# SCH_12V-DC-Distribute_2025-02-16_1.net
KiCad netlist of a schematic drawn in EasyEDA
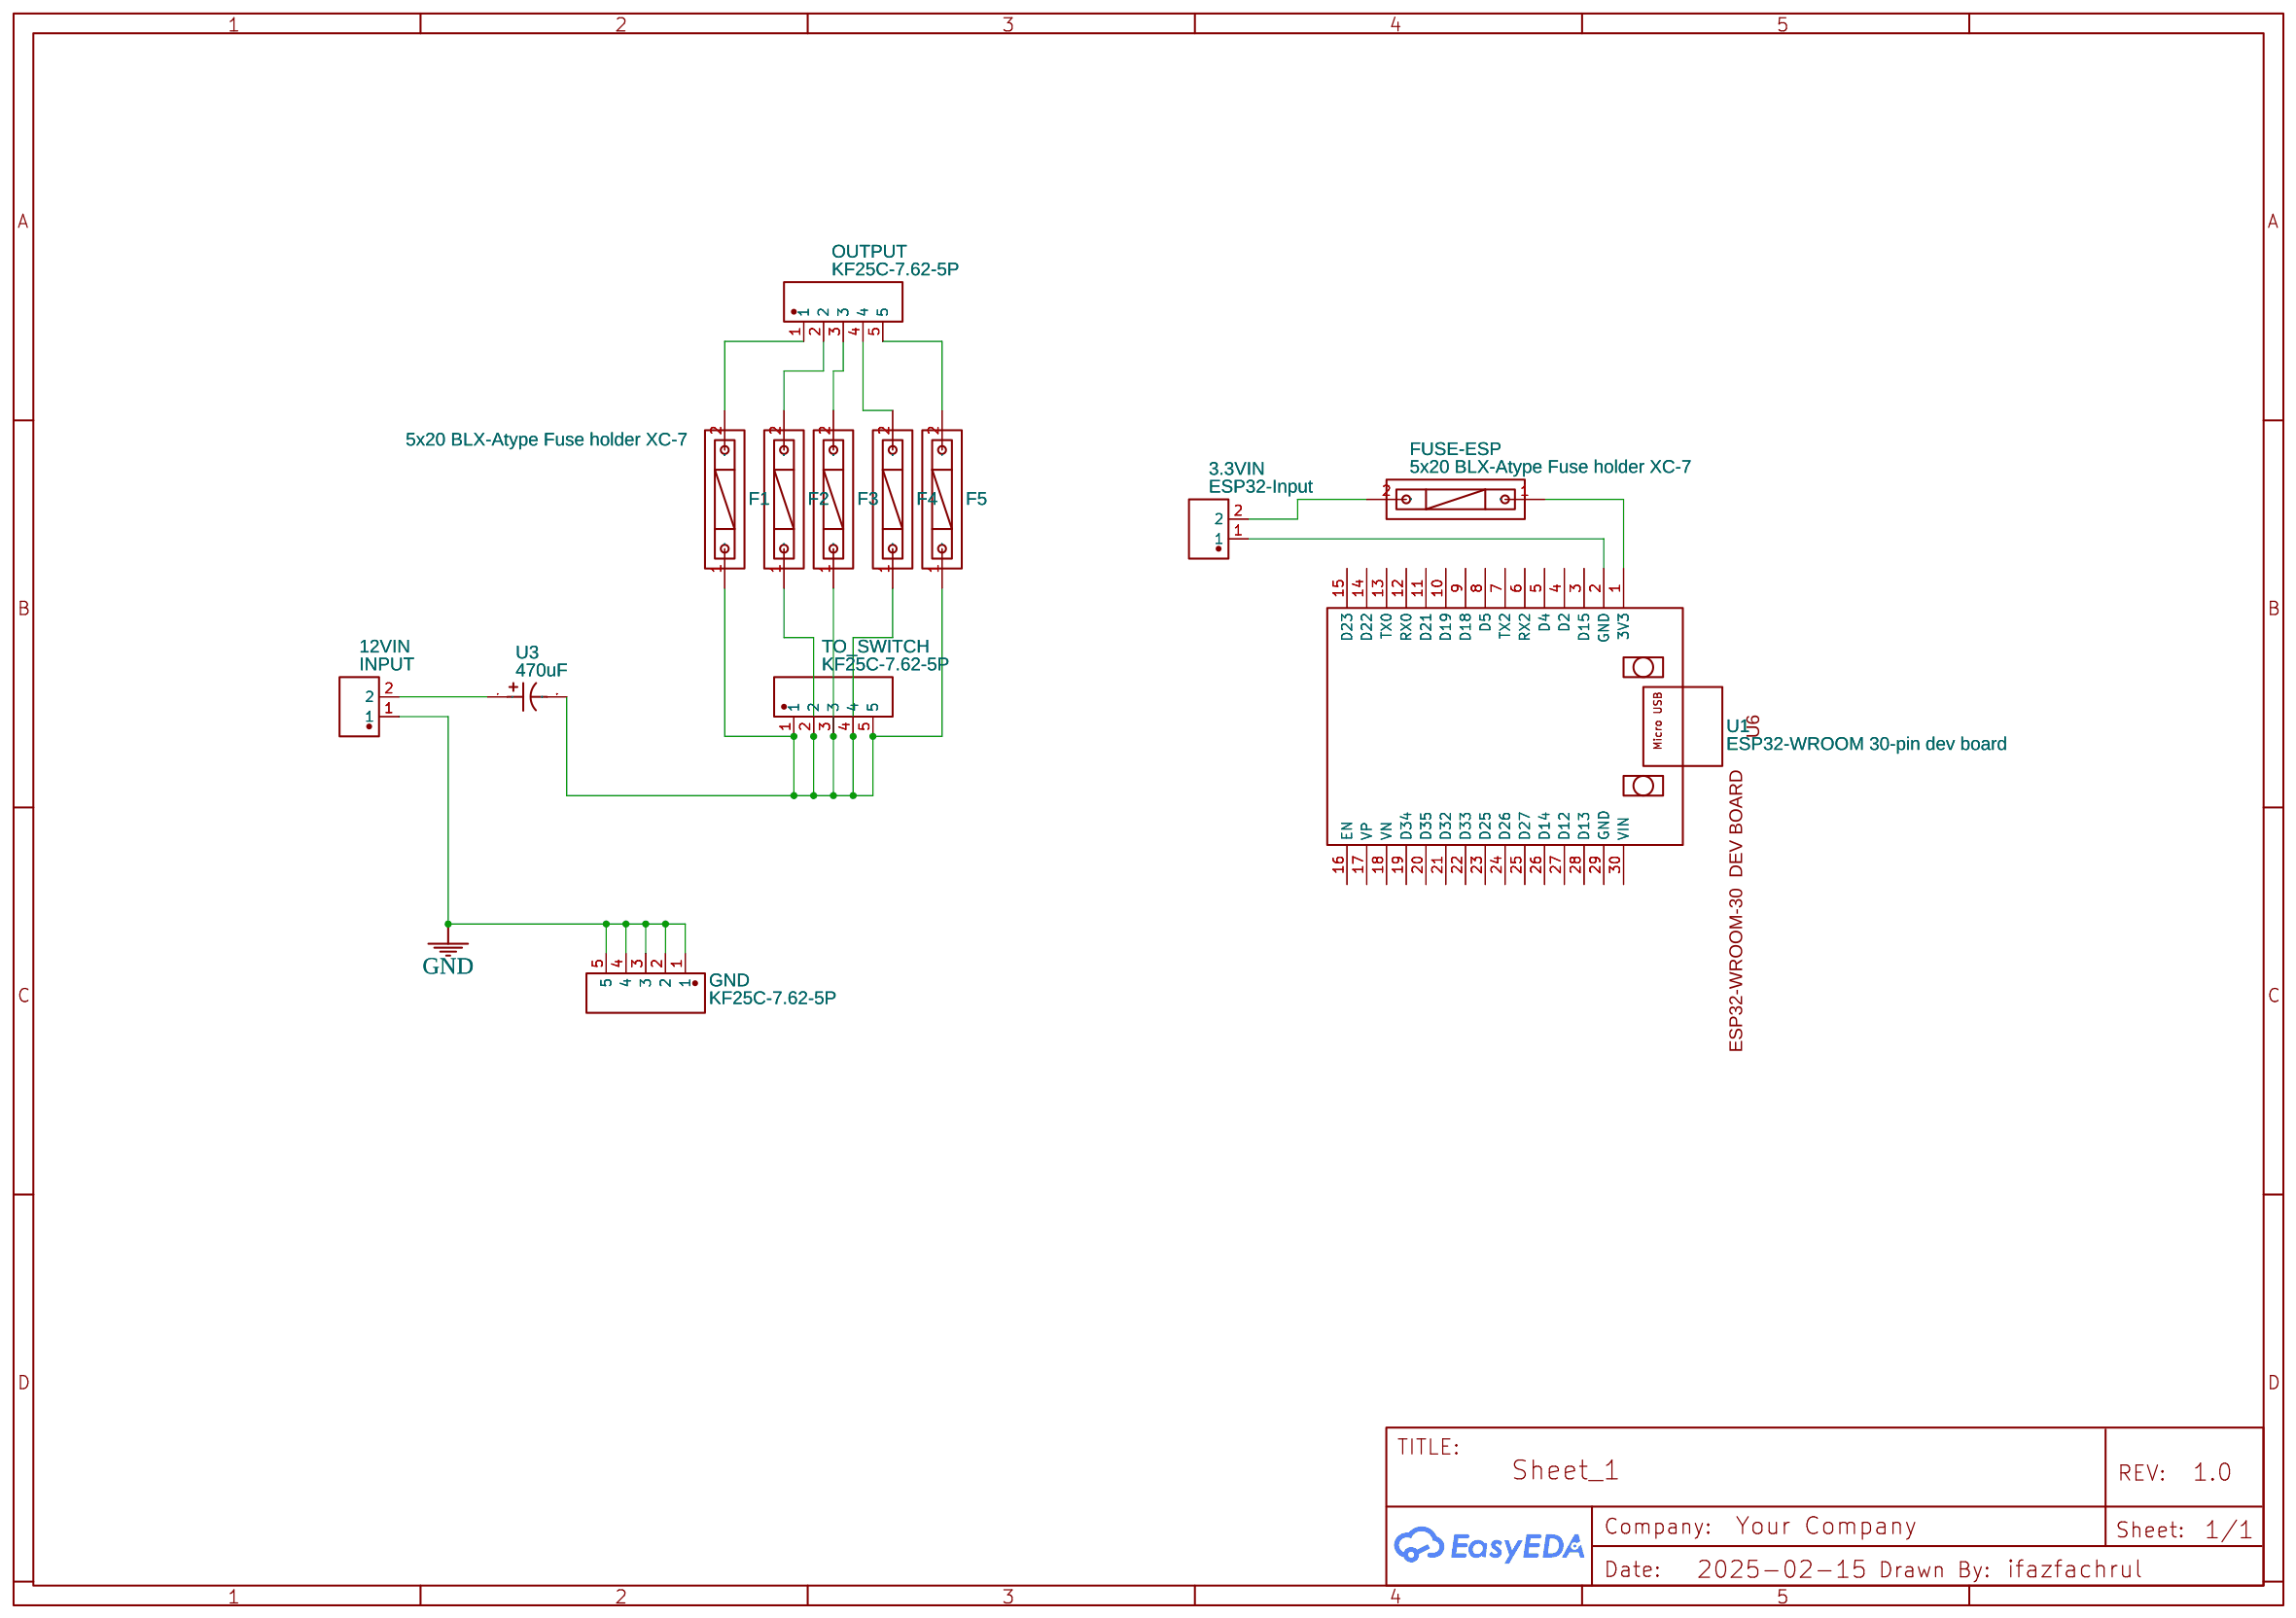
[diagram p0: schematic sheet]

(export (version "E")
  (design (tool "Eeschema 10.0.6"))
  (components
    (comp (ref "3.3VIN")
      (value "ESP32-Input")
      (fields (field (name "Manufacturer Part") "KF25H-7.62-2P") (field (name "Manufacturer") "KEFA(科发)"))
      (libsource (lib "") (part "KF25H-7.62-2P"))
    )
    (comp (ref "12VIN")
      (value "INPUT")
      (fields (field (name "Manufacturer Part") "KF25H-7.62-2P") (field (name "Manufacturer") "KEFA(科发)"))
      (libsource (lib "") (part "KF25H-7.62-2P_1"))
    )
    (comp (ref "F1")
      (value "5x20 BLX-Atype Fuse holder XC-7")
      (fields
        (field (name "Manufacturer Part") "5x20 BLX-A型 保险丝支架 XC-7")
        (field (name "Manufacturer") "xcfuse(旭程)")
      )
      (libsource (lib "") (part "5x20 BLX-Atype Fuse holder XC-7"))
    )
    (comp (ref "F2")
      (value "5x20 BLX-Atype Fuse holder XC-7")
      (fields
        (field (name "Manufacturer Part") "5x20 BLX-A型 保险丝支架 XC-7")
        (field (name "Manufacturer") "xcfuse(旭程)")
      )
      (libsource (lib "") (part "5x20 BLX-Atype Fuse holder XC-7"))
    )
    (comp (ref "F3")
      (value "5x20 BLX-Atype Fuse holder XC-7")
      (fields
        (field (name "Manufacturer Part") "5x20 BLX-A型 保险丝支架 XC-7")
        (field (name "Manufacturer") "xcfuse(旭程)")
      )
      (libsource (lib "") (part "5x20 BLX-Atype Fuse holder XC-7"))
    )
    (comp (ref "F4")
      (value "5x20 BLX-Atype Fuse holder XC-7")
      (fields
        (field (name "Manufacturer Part") "5x20 BLX-A型 保险丝支架 XC-7")
        (field (name "Manufacturer") "xcfuse(旭程)")
      )
      (libsource (lib "") (part "5x20 BLX-Atype Fuse holder XC-7"))
    )
    (comp (ref "F5")
      (value "5x20 BLX-Atype Fuse holder XC-7")
      (fields
        (field (name "Manufacturer Part") "5x20 BLX-A型 保险丝支架 XC-7")
        (field (name "Manufacturer") "xcfuse(旭程)")
      )
      (libsource (lib "") (part "5x20 BLX-Atype Fuse holder XC-7"))
    )
    (comp (ref "FUSE-ESP")
      (value "5x20 BLX-Atype Fuse holder XC-7")
      (fields
        (field (name "Manufacturer Part") "5x20 BLX-A型 保险丝支架 XC-7")
        (field (name "Manufacturer") "xcfuse(旭程)")
      )
      (libsource (lib "") (part "5x20 BLX-Atype Fuse holder XC-7_1"))
    )
    (comp (ref "GND")
      (value "KF25C-7.62-5P")
      (fields (field (name "Manufacturer") "KEFA(科发)"))
      (libsource (lib "") (part "KF25C-7.62-5P_2"))
    )
    (comp (ref "OUTPUT")
      (value "KF25C-7.62-5P")
      (fields (field (name "Manufacturer") "KEFA(科发)"))
      (libsource (lib "") (part "KF25C-7.62-5P"))
    )
    (comp (ref "TO_SWITCH")
      (value "KF25C-7.62-5P")
      (fields (field (name "Manufacturer") "KEFA(科发)"))
      (libsource (lib "") (part "KF25C-7.62-5P_1"))
    )
    (comp (ref "U1")
      (value "ESP32-WROOM 30-pin dev board")
      (libsource (lib "") (part "ESP32-WROOM 30-pin dev board"))
    )
    (comp (ref "U3")
      (value "470uF")
      (fields
        (field (name "Manufacturer Part") "VT470UF16V167RV0135")
        (field (name "Manufacturer") "KNSCHA(科尼盛)")
      )
      (libsource (lib "") (part "VT470UF16V167RV0135"))
    )
  )
  (nets
    (net (code "1") (name "GND") (class "Default")
      (node (ref "12VIN") (pin "1") (pinfunction "1_1") (pintype "unspecified"))
      (node (ref "GND") (pin "1") (pinfunction "1_1") (pintype "unspecified"))
      (node (ref "GND") (pin "2") (pinfunction "2_2") (pintype "unspecified"))
      (node (ref "GND") (pin "3") (pinfunction "3_3") (pintype "unspecified"))
      (node (ref "GND") (pin "4") (pinfunction "4_4") (pintype "unspecified"))
      (node (ref "GND") (pin "5") (pinfunction "5_5") (pintype "unspecified"))
    )
    (net (code "2") (name "Net-(3.3VIN-Pad1)") (class "Default")
      (node (ref "3.3VIN") (pin "1") (pinfunction "1_1") (pintype "unspecified"))
      (node (ref "U1") (pin "2") (pinfunction "GND_2") (pintype "unspecified"))
    )
    (net (code "3") (name "Net-(3.3VIN-Pad2)") (class "Default")
      (node (ref "3.3VIN") (pin "2") (pinfunction "2_2") (pintype "unspecified"))
      (node (ref "FUSE-ESP") (pin "2") (pinfunction "2_2") (pintype "unspecified"))
    )
    (net (code "4") (name "Net-(12VIN-Pad2)") (class "Default")
      (node (ref "12VIN") (pin "2") (pinfunction "2_2") (pintype "unspecified"))
      (node (ref "U3") (pin "1") (pinfunction "1_1") (pintype "input"))
    )
    (net (code "5") (name "Net-(F1-Pad1)") (class "Default")
      (node (ref "F1") (pin "1") (pinfunction "1_1") (pintype "unspecified"))
      (node (ref "F2") (pin "1") (pinfunction "1_1") (pintype "unspecified"))
      (node (ref "F3") (pin "1") (pinfunction "1_1") (pintype "unspecified"))
      (node (ref "F4") (pin "1") (pinfunction "1_1") (pintype "unspecified"))
      (node (ref "F5") (pin "1") (pinfunction "1_1") (pintype "unspecified"))
      (node (ref "TO_SWITCH") (pin "1") (pinfunction "1_1") (pintype "unspecified"))
      (node (ref "TO_SWITCH") (pin "2") (pinfunction "2_2") (pintype "unspecified"))
      (node (ref "TO_SWITCH") (pin "3") (pinfunction "3_3") (pintype "unspecified"))
      (node (ref "TO_SWITCH") (pin "4") (pinfunction "4_4") (pintype "unspecified"))
      (node (ref "TO_SWITCH") (pin "5") (pinfunction "5_5") (pintype "unspecified"))
      (node (ref "U3") (pin "2") (pinfunction "2_2") (pintype "input"))
    )
    (net (code "6") (name "Net-(F1-Pad2)") (class "Default")
      (node (ref "F1") (pin "2") (pinfunction "2_2") (pintype "unspecified"))
      (node (ref "OUTPUT") (pin "1") (pinfunction "1_1") (pintype "unspecified"))
    )
    (net (code "7") (name "Net-(F2-Pad2)") (class "Default")
      (node (ref "F2") (pin "2") (pinfunction "2_2") (pintype "unspecified"))
      (node (ref "OUTPUT") (pin "2") (pinfunction "2_2") (pintype "unspecified"))
    )
    (net (code "8") (name "Net-(F3-Pad2)") (class "Default")
      (node (ref "F3") (pin "2") (pinfunction "2_2") (pintype "unspecified"))
      (node (ref "OUTPUT") (pin "3") (pinfunction "3_3") (pintype "unspecified"))
    )
    (net (code "9") (name "Net-(F4-Pad2)") (class "Default")
      (node (ref "F4") (pin "2") (pinfunction "2_2") (pintype "unspecified"))
      (node (ref "OUTPUT") (pin "4") (pinfunction "4_4") (pintype "unspecified"))
    )
    (net (code "10") (name "Net-(F5-Pad2)") (class "Default")
      (node (ref "F5") (pin "2") (pinfunction "2_2") (pintype "unspecified"))
      (node (ref "OUTPUT") (pin "5") (pinfunction "5_5") (pintype "unspecified"))
    )
    (net (code "11") (name "Net-(U1-3V3)") (class "Default")
      (node (ref "FUSE-ESP") (pin "1") (pinfunction "1_1") (pintype "unspecified"))
      (node (ref "U1") (pin "1") (pinfunction "3V3_1") (pintype "unspecified"))
    )
    (net (code "12") (name "unconnected-(U1-D2-Pad4)") (class "Default")
      (node (ref "U1") (pin "4") (pinfunction "D2_4") (pintype "unspecified"))
    )
    (net (code "13") (name "unconnected-(U1-D4-Pad5)") (class "Default")
      (node (ref "U1") (pin "5") (pinfunction "D4_5") (pintype "unspecified"))
    )
    (net (code "14") (name "unconnected-(U1-D5-Pad8)") (class "Default")
      (node (ref "U1") (pin "8") (pinfunction "D5_8") (pintype "unspecified"))
    )
    (net (code "15") (name "unconnected-(U1-D12-Pad27)") (class "Default")
      (node (ref "U1") (pin "27") (pinfunction "D12_27") (pintype "unspecified"))
    )
    (net (code "16") (name "unconnected-(U1-D13-Pad28)") (class "Default")
      (node (ref "U1") (pin "28") (pinfunction "D13_28") (pintype "unspecified"))
    )
    (net (code "17") (name "unconnected-(U1-D14-Pad26)") (class "Default")
      (node (ref "U1") (pin "26") (pinfunction "D14_26") (pintype "unspecified"))
    )
    (net (code "18") (name "unconnected-(U1-D15-Pad3)") (class "Default")
      (node (ref "U1") (pin "3") (pinfunction "D15_3") (pintype "unspecified"))
    )
    (net (code "19") (name "unconnected-(U1-D18-Pad9)") (class "Default")
      (node (ref "U1") (pin "9") (pinfunction "D18_9") (pintype "unspecified"))
    )
    (net (code "20") (name "unconnected-(U1-D19-Pad10)") (class "Default")
      (node (ref "U1") (pin "10") (pinfunction "D19_10") (pintype "unspecified"))
    )
    (net (code "21") (name "unconnected-(U1-D21-Pad11)") (class "Default")
      (node (ref "U1") (pin "11") (pinfunction "D21_11") (pintype "unspecified"))
    )
    (net (code "22") (name "unconnected-(U1-D22-Pad14)") (class "Default")
      (node (ref "U1") (pin "14") (pinfunction "D22_14") (pintype "unspecified"))
    )
    (net (code "23") (name "unconnected-(U1-D23-Pad15)") (class "Default")
      (node (ref "U1") (pin "15") (pinfunction "D23_15") (pintype "unspecified"))
    )
    (net (code "24") (name "unconnected-(U1-D25-Pad23)") (class "Default")
      (node (ref "U1") (pin "23") (pinfunction "D25_23") (pintype "unspecified"))
    )
    (net (code "25") (name "unconnected-(U1-D26-Pad24)") (class "Default")
      (node (ref "U1") (pin "24") (pinfunction "D26_24") (pintype "unspecified"))
    )
    (net (code "26") (name "unconnected-(U1-D27-Pad25)") (class "Default")
      (node (ref "U1") (pin "25") (pinfunction "D27_25") (pintype "unspecified"))
    )
    (net (code "27") (name "unconnected-(U1-D32-Pad21)") (class "Default")
      (node (ref "U1") (pin "21") (pinfunction "D32_21") (pintype "unspecified"))
    )
    (net (code "28") (name "unconnected-(U1-D33-Pad22)") (class "Default")
      (node (ref "U1") (pin "22") (pinfunction "D33_22") (pintype "unspecified"))
    )
    (net (code "29") (name "unconnected-(U1-D34-Pad19)") (class "Default")
      (node (ref "U1") (pin "19") (pinfunction "D34_19") (pintype "unspecified"))
    )
    (net (code "30") (name "unconnected-(U1-D35-Pad20)") (class "Default")
      (node (ref "U1") (pin "20") (pinfunction "D35_20") (pintype "unspecified"))
    )
    (net (code "31") (name "unconnected-(U1-EN-Pad16)") (class "Default")
      (node (ref "U1") (pin "16") (pinfunction "EN_16") (pintype "unspecified"))
    )
    (net (code "32") (name "unconnected-(U1-GND-Pad29)") (class "Default")
      (node (ref "U1") (pin "29") (pinfunction "GND_29") (pintype "unspecified"))
    )
    (net (code "33") (name "unconnected-(U1-RX0-Pad12)") (class "Default")
      (node (ref "U1") (pin "12") (pinfunction "RX0_12") (pintype "unspecified"))
    )
    (net (code "34") (name "unconnected-(U1-RX2-Pad6)") (class "Default")
      (node (ref "U1") (pin "6") (pinfunction "RX2_6") (pintype "unspecified"))
    )
    (net (code "35") (name "unconnected-(U1-TX0-Pad13)") (class "Default")
      (node (ref "U1") (pin "13") (pinfunction "TX0_13") (pintype "unspecified"))
    )
    (net (code "36") (name "unconnected-(U1-TX2-Pad7)") (class "Default")
      (node (ref "U1") (pin "7") (pinfunction "TX2_7") (pintype "unspecified"))
    )
    (net (code "37") (name "unconnected-(U1-VIN-Pad30)") (class "Default")
      (node (ref "U1") (pin "30") (pinfunction "VIN_30") (pintype "unspecified"))
    )
    (net (code "38") (name "unconnected-(U1-VN-Pad18)") (class "Default")
      (node (ref "U1") (pin "18") (pinfunction "VN_18") (pintype "unspecified"))
    )
    (net (code "39") (name "unconnected-(U1-VP-Pad17)") (class "Default")
      (node (ref "U1") (pin "17") (pinfunction "VP_17") (pintype "unspecified"))
    )
  )
)
